# ArduinoUnoShield.net
KiCad netlist of a schematic drawn in Altium Designer
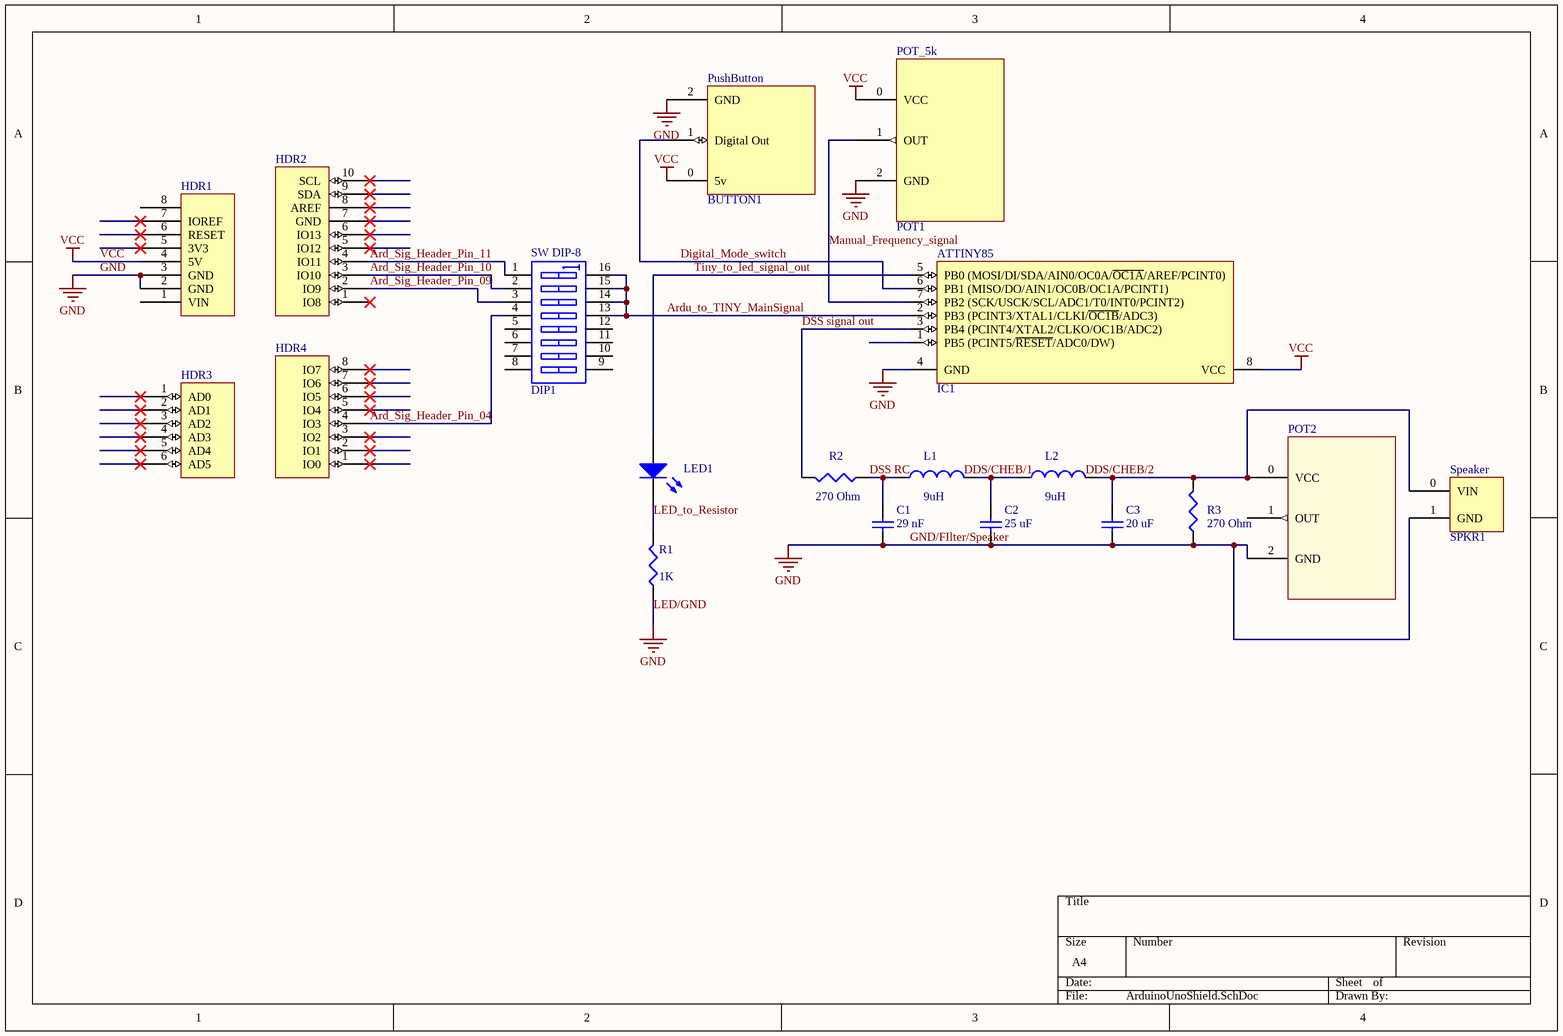
[diagram p0: ArduinoUnoShield.SchDoc]

(export (version "E")
  (design (tool "Eeschema 10.0.6"))
  (components
    (comp (ref "ATTINY85")
      (value "IC1")
      (footprint "DIP-8")
      (fields (field (name "PUBLISHER") "Altium Limited"))
      (libsource (lib "Atmel Microcontroller 8-Bit tinyAVR") (part "ATtiny85-20PU"))
    )
    (comp (ref "C1")
      (value "29 nF")
      (footprint "1608[0603]")
      (description "Capacitor (Semiconductor SIM Model)")
      (fields (field (name "Comment") "Cap Semi") (field (name "PUBLISHER") "Altium Limited"))
      (libsource (lib "Miscellaneous Devices") (part "Cap Semi"))
    )
    (comp (ref "C2")
      (value "25 uF")
      (footprint "1608[0603]")
      (description "Capacitor (Semiconductor SIM Model)")
      (fields (field (name "Comment") "Cap Semi") (field (name "PUBLISHER") "Altium Limited"))
      (libsource (lib "Miscellaneous Devices") (part "Cap Semi"))
    )
    (comp (ref "C3")
      (value "20 uF")
      (footprint "1608[0603]")
      (description "Capacitor (Semiconductor SIM Model)")
      (fields (field (name "Comment") "Cap Semi") (field (name "PUBLISHER") "Altium Limited"))
      (libsource (lib "Miscellaneous Devices") (part "Cap Semi"))
    )
    (comp (ref "HDR1")
      (value "POWER_UNO")
      (footprint "Header 8x1 8.5mm")
      (libsource (lib "Header") (part "POWER_UNO"))
    )
    (comp (ref "HDR2")
      (value "IOH")
      (footprint "Header:Header 10x1 8.5mm")
      (libsource (lib "Header") (part "IOH"))
    )
    (comp (ref "HDR3")
      (value "AD")
      (footprint "Header:Header 6x1 8.5mm")
      (libsource (lib "Header") (part "AD"))
    )
    (comp (ref "HDR4") (value "IOL") (footprint "Header 8x1 8.5mm") (libsource (lib "Header") (part "IOL")))
    (comp (ref "L1")
      (value "9uH")
      (footprint "AXIAL-0.3")
      (description "Inductor")
      (fields (field (name "PUBLISHER") "Altium Limited"))
      (libsource (lib "Miscellaneous Devices") (part "Inductor"))
    )
    (comp (ref "L2")
      (value "9uH")
      (footprint "AXIAL-0.3")
      (description "Inductor")
      (fields (field (name "PUBLISHER") "Altium Limited"))
      (libsource (lib "Miscellaneous Devices") (part "Inductor"))
    )
    (comp (ref "LED1")
      (value "LED1")
      (footprint "LED-1")
      (description "Typical RED GaAs LED")
      (fields (field (name "PUBLISHER") "Altium Limited"))
      (libsource (lib "Miscellaneous Devices") (part "LED1"))
    )
    (comp (ref "POT2")
      (value "Component_1")
      (footprint "POT Footprint_Rev_1")
      (description "5k RES")
      (libsource (lib "PotLib_Rev_5") (part "Component_1"))
    )
    (comp (ref "POT_5k")
      (value "POT1")
      (footprint "POT Footprint_Rev_1")
      (description "5k RES")
      (libsource (lib "PotLib_Rev_5") (part "Component_1"))
    )
    (comp (ref "PushButton")
      (value "BUTTON1")
      (footprint "PushButtonFrame")
      (libsource (lib "Pushbutton_V_5") (part "PushButton"))
    )
    (comp (ref "R1")
      (value "1K")
      (footprint "J1-0603")
      (description "Resistor")
      (fields (field (name "PUBLISHER") "Altium Limited"))
      (libsource (lib "Miscellaneous Devices") (part "Res3"))
    )
    (comp (ref "R2")
      (value "270 Ohm")
      (footprint "J1-0603")
      (description "Resistor")
      (fields (field (name "Comment") "Res3") (field (name "PUBLISHER") "Altium Limited"))
      (libsource (lib "Miscellaneous Devices") (part "Res3"))
    )
    (comp (ref "R3")
      (value "270 Ohm")
      (footprint "J1-0603")
      (description "Resistor")
      (fields (field (name "Comment") "Res3") (field (name "PUBLISHER") "Altium Limited"))
      (libsource (lib "Miscellaneous Devices") (part "Res3"))
    )
    (comp (ref "Speaker")
      (value "SPKR1")
      (footprint "PCBComponent_1")
      (libsource (lib "Schlib1_rev_01") (part "Component_1"))
    )
    (comp (ref "SW DIP-8")
      (value "DIP1")
      (footprint "DIP_SW_8WAY_SMD")
      (description "DIP Switch, 8 Position, SPST")
      (fields (field (name "PUBLISHER") "Altium Limited"))
      (libsource (lib "Miscellaneous Devices") (part "SW DIP-8"))
    )
  )
  (nets
    (net (code "2") (name "/Ard_Sig_Header_Pin_04") (class "Default")
      (node (ref "HDR4") (pin "4") (pinfunction "IO3_4") (pintype "bidirectional"))
      (node (ref "SW DIP-8") (pin "4") (pinfunction "A4_4") (pintype "passive"))
    )
    (net (code "3") (name "/Ard_Sig_Header_Pin_09") (class "Default")
      (node (ref "HDR2") (pin "2") (pinfunction "IO9_2") (pintype "bidirectional"))
      (node (ref "SW DIP-8") (pin "3") (pinfunction "A3_3") (pintype "passive"))
    )
    (net (code "4") (name "/Ard_Sig_Header_Pin_10") (class "Default")
      (node (ref "HDR2") (pin "3") (pinfunction "IO10_3") (pintype "bidirectional"))
      (node (ref "SW DIP-8") (pin "2") (pinfunction "A2_2") (pintype "passive"))
    )
    (net (code "5") (name "/Ard_Sig_Header_Pin_11") (class "Default")
      (node (ref "HDR2") (pin "4") (pinfunction "IO11_4") (pintype "bidirectional"))
      (node (ref "SW DIP-8") (pin "1") (pinfunction "A1_1") (pintype "passive"))
    )
    (net (code "6") (name "/Ardu_to_TINY_MainSignal") (class "Default")
      (node (ref "ATTINY85") (pin "2") (pinfunction "PB3_(PCINT3/XTAL1/CLKI/~{OC1B}/ADC3)_2") (pintype "bidirectional"))
      (node (ref "SW DIP-8") (pin "13") (pinfunction "B4_13") (pintype "passive"))
      (node (ref "SW DIP-8") (pin "14") (pinfunction "B3_14") (pintype "passive"))
      (node (ref "SW DIP-8") (pin "15") (pinfunction "B2_15") (pintype "passive"))
      (node (ref "SW DIP-8") (pin "16") (pinfunction "B1_16") (pintype "passive"))
    )
    (net (code "9") (name "/DSS RC") (class "Default")
      (node (ref "C1") (pin "2") (pinfunction "2_2") (pintype "passive"))
      (node (ref "L1") (pin "1") (pinfunction "1_1") (pintype "passive"))
      (node (ref "R2") (pin "1") (pinfunction "1_1") (pintype "passive"))
    )
    (net (code "10") (name "/DSS signal out") (class "Default")
      (node (ref "ATTINY85") (pin "3") (pinfunction "PB4_(PCINT4/XTAL2/CLKO/OC1B/ADC2)_3") (pintype "bidirectional"))
      (node (ref "R2") (pin "2") (pinfunction "2_2") (pintype "passive"))
    )
    (net (code "11") (name "/Digital_Mode_switch") (class "Default")
      (node (ref "ATTINY85") (pin "6") (pinfunction "PB1_(MISO/DO/AIN1/OC0B/OC1A/PCINT1)_6") (pintype "bidirectional"))
      (node (ref "PushButton") (pin "1") (pinfunction "Digital_Out_1") (pintype "bidirectional"))
    )
    (net (code "12") (name "/LED_to_Resistor") (class "Default")
      (node (ref "LED1") (pin "2") (pinfunction "K_2") (pintype "passive"))
      (node (ref "R1") (pin "2") (pinfunction "2_2") (pintype "passive"))
    )
    (net (code "13") (name "/Manual_Frequency_signal") (class "Default")
      (node (ref "ATTINY85") (pin "7") (pinfunction "PB2_(SCK/USCK/SCL/ADC1/T0/INT0/PCINT2)_7") (pintype "bidirectional"))
      (node (ref "POT_5k") (pin "1") (pinfunction "OUT_1") (pintype "output"))
    )
    (net (code "14") (name "/Tiny_to_led_signal_out") (class "Default")
      (node (ref "ATTINY85") (pin "5") (pinfunction "PB0_(MOSI/DI/SDA/AIN0/OC0A/~{OC1A}/AREF/PCINT0)_5") (pintype "bidirectional"))
      (node (ref "LED1") (pin "1") (pinfunction "A_1") (pintype "passive"))
    )
    (net (code "15") (name "GND") (class "Default")
      (node (ref "ATTINY85") (pin "4") (pinfunction "GND_4") (pintype "power_in"))
      (node (ref "C1") (pin "1") (pinfunction "1_1") (pintype "passive"))
      (node (ref "C2") (pin "1") (pinfunction "1_1") (pintype "passive"))
      (node (ref "C3") (pin "1") (pinfunction "1_1") (pintype "passive"))
      (node (ref "HDR1") (pin "2") (pinfunction "GND_2") (pintype "power_in"))
      (node (ref "HDR1") (pin "3") (pinfunction "GND_3") (pintype "power_in"))
      (node (ref "POT2") (pin "2") (pinfunction "GND_2") (pintype "power_in"))
      (node (ref "POT_5k") (pin "2") (pinfunction "GND_2") (pintype "power_in"))
      (node (ref "PushButton") (pin "2") (pinfunction "GND_2") (pintype "power_in"))
      (node (ref "R1") (pin "1") (pinfunction "1_1") (pintype "passive"))
      (node (ref "R3") (pin "1") (pinfunction "1_1") (pintype "passive"))
      (node (ref "Speaker") (pin "1") (pinfunction "GND_1") (pintype "power_in"))
    )
    (net (code "16") (name "Net-(C2-Pad2)") (class "Default")
      (node (ref "C2") (pin "2") (pinfunction "2_2") (pintype "passive"))
      (node (ref "L1") (pin "2") (pinfunction "2_2") (pintype "passive"))
      (node (ref "L2") (pin "1") (pinfunction "1_1") (pintype "passive"))
    )
    (net (code "17") (name "Net-(POT2-VCC)") (class "Default")
      (node (ref "C3") (pin "2") (pinfunction "2_2") (pintype "passive"))
      (node (ref "L2") (pin "2") (pinfunction "2_2") (pintype "passive"))
      (node (ref "POT2") (pin "0") (pinfunction "VCC_0") (pintype "power_in"))
      (node (ref "R3") (pin "2") (pinfunction "2_2") (pintype "passive"))
      (node (ref "Speaker") (pin "0") (pinfunction "VIN_0") (pintype "power_in"))
    )
    (net (code "18") (name "VCC") (class "Default")
      (node (ref "ATTINY85") (pin "8") (pinfunction "VCC_8") (pintype "power_in"))
      (node (ref "HDR1") (pin "4") (pinfunction "5V_4") (pintype "power_in"))
      (node (ref "POT_5k") (pin "0") (pinfunction "VCC_0") (pintype "power_in"))
      (node (ref "PushButton") (pin "0") (pinfunction "5v_0") (pintype "power_in"))
    )
    (net (code "19") (name "unconnected-(ATTINY85-PB5_(PCINT5{slash}~{RESET}{slash}ADC0{slash}DW)-Pad1)") (class "Default")
      (node (ref "ATTINY85") (pin "1") (pinfunction "PB5_(PCINT5/~{RESET}/ADC0/DW)_1") (pintype "bidirectional"))
    )
    (net (code "20") (name "unconnected-(HDR1-3V3-Pad5)") (class "Default")
      (node (ref "HDR1") (pin "5") (pinfunction "3V3_5") (pintype "power_in+no_connect"))
    )
    (net (code "21") (name "unconnected-(HDR1-IOREF-Pad7)") (class "Default")
      (node (ref "HDR1") (pin "7") (pinfunction "IOREF_7") (pintype "power_in+no_connect"))
    )
    (net (code "22") (name "unconnected-(HDR1-Pad8)") (class "Default")
      (node (ref "HDR1") (pin "8") (pintype "passive"))
    )
    (net (code "23") (name "unconnected-(HDR1-RESET-Pad6)") (class "Default")
      (node (ref "HDR1") (pin "6") (pinfunction "RESET_6") (pintype "passive+no_connect"))
    )
    (net (code "24") (name "unconnected-(HDR1-VIN-Pad1)") (class "Default")
      (node (ref "HDR1") (pin "1") (pinfunction "VIN_1") (pintype "power_in"))
    )
    (net (code "25") (name "unconnected-(HDR2-AREF-Pad8)") (class "Default")
      (node (ref "HDR2") (pin "8") (pinfunction "AREF_8") (pintype "passive+no_connect"))
    )
    (net (code "26") (name "unconnected-(HDR2-GND-Pad7)") (class "Default")
      (node (ref "HDR2") (pin "7") (pinfunction "GND_7") (pintype "power_in+no_connect"))
    )
    (net (code "27") (name "unconnected-(HDR2-IO8-Pad1)") (class "Default")
      (node (ref "HDR2") (pin "1") (pinfunction "IO8_1") (pintype "bidirectional+no_connect"))
    )
    (net (code "28") (name "unconnected-(HDR2-IO12-Pad5)") (class "Default")
      (node (ref "HDR2") (pin "5") (pinfunction "IO12_5") (pintype "bidirectional+no_connect"))
    )
    (net (code "29") (name "unconnected-(HDR2-IO13-Pad6)") (class "Default")
      (node (ref "HDR2") (pin "6") (pinfunction "IO13_6") (pintype "bidirectional+no_connect"))
    )
    (net (code "30") (name "unconnected-(HDR2-SCL-Pad10)") (class "Default")
      (node (ref "HDR2") (pin "10") (pinfunction "SCL_10") (pintype "bidirectional+no_connect"))
    )
    (net (code "31") (name "unconnected-(HDR2-SDA-Pad9)") (class "Default")
      (node (ref "HDR2") (pin "9") (pinfunction "SDA_9") (pintype "bidirectional+no_connect"))
    )
    (net (code "32") (name "unconnected-(HDR3-AD0-Pad1)") (class "Default")
      (node (ref "HDR3") (pin "1") (pinfunction "AD0_1") (pintype "bidirectional+no_connect"))
    )
    (net (code "33") (name "unconnected-(HDR3-AD1-Pad2)") (class "Default")
      (node (ref "HDR3") (pin "2") (pinfunction "AD1_2") (pintype "bidirectional+no_connect"))
    )
    (net (code "34") (name "unconnected-(HDR3-AD2-Pad3)") (class "Default")
      (node (ref "HDR3") (pin "3") (pinfunction "AD2_3") (pintype "bidirectional+no_connect"))
    )
    (net (code "35") (name "unconnected-(HDR3-AD3-Pad4)") (class "Default")
      (node (ref "HDR3") (pin "4") (pinfunction "AD3_4") (pintype "bidirectional+no_connect"))
    )
    (net (code "36") (name "unconnected-(HDR3-AD4-Pad5)") (class "Default")
      (node (ref "HDR3") (pin "5") (pinfunction "AD4_5") (pintype "bidirectional+no_connect"))
    )
    (net (code "37") (name "unconnected-(HDR3-AD5-Pad6)") (class "Default")
      (node (ref "HDR3") (pin "6") (pinfunction "AD5_6") (pintype "bidirectional+no_connect"))
    )
    (net (code "38") (name "unconnected-(HDR4-IO0-Pad1)") (class "Default")
      (node (ref "HDR4") (pin "1") (pinfunction "IO0_1") (pintype "bidirectional+no_connect"))
    )
    (net (code "39") (name "unconnected-(HDR4-IO1-Pad2)") (class "Default")
      (node (ref "HDR4") (pin "2") (pinfunction "IO1_2") (pintype "bidirectional+no_connect"))
    )
    (net (code "40") (name "unconnected-(HDR4-IO2-Pad3)") (class "Default")
      (node (ref "HDR4") (pin "3") (pinfunction "IO2_3") (pintype "bidirectional+no_connect"))
    )
    (net (code "41") (name "unconnected-(HDR4-IO4-Pad5)") (class "Default")
      (node (ref "HDR4") (pin "5") (pinfunction "IO4_5") (pintype "bidirectional+no_connect"))
    )
    (net (code "42") (name "unconnected-(HDR4-IO5-Pad6)") (class "Default")
      (node (ref "HDR4") (pin "6") (pinfunction "IO5_6") (pintype "bidirectional+no_connect"))
    )
    (net (code "43") (name "unconnected-(HDR4-IO6-Pad7)") (class "Default")
      (node (ref "HDR4") (pin "7") (pinfunction "IO6_7") (pintype "bidirectional+no_connect"))
    )
    (net (code "44") (name "unconnected-(HDR4-IO7-Pad8)") (class "Default")
      (node (ref "HDR4") (pin "8") (pinfunction "IO7_8") (pintype "bidirectional+no_connect"))
    )
    (net (code "45") (name "unconnected-(POT2-OUT-Pad1)") (class "Default")
      (node (ref "POT2") (pin "1") (pinfunction "OUT_1") (pintype "output"))
    )
    (net (code "46") (name "unconnected-(SW DIP-8-A5-Pad5)") (class "Default")
      (node (ref "SW DIP-8") (pin "5") (pinfunction "A5_5") (pintype "passive"))
    )
    (net (code "47") (name "unconnected-(SW DIP-8-A6-Pad6)") (class "Default")
      (node (ref "SW DIP-8") (pin "6") (pinfunction "A6_6") (pintype "passive"))
    )
    (net (code "48") (name "unconnected-(SW DIP-8-A7-Pad7)") (class "Default")
      (node (ref "SW DIP-8") (pin "7") (pinfunction "A7_7") (pintype "passive"))
    )
    (net (code "49") (name "unconnected-(SW DIP-8-A8-Pad8)") (class "Default")
      (node (ref "SW DIP-8") (pin "8") (pinfunction "A8_8") (pintype "passive"))
    )
    (net (code "50") (name "unconnected-(SW DIP-8-B5-Pad12)") (class "Default")
      (node (ref "SW DIP-8") (pin "12") (pinfunction "B5_12") (pintype "passive"))
    )
    (net (code "51") (name "unconnected-(SW DIP-8-B6-Pad11)") (class "Default")
      (node (ref "SW DIP-8") (pin "11") (pinfunction "B6_11") (pintype "passive"))
    )
    (net (code "52") (name "unconnected-(SW DIP-8-B7-Pad10)") (class "Default")
      (node (ref "SW DIP-8") (pin "10") (pinfunction "B7_10") (pintype "passive"))
    )
    (net (code "53") (name "unconnected-(SW DIP-8-B8-Pad9)") (class "Default")
      (node (ref "SW DIP-8") (pin "9") (pinfunction "B8_9") (pintype "passive"))
    )
  )
)
